# Sheet1.net
KiCad netlist of a schematic drawn in Altium Designer
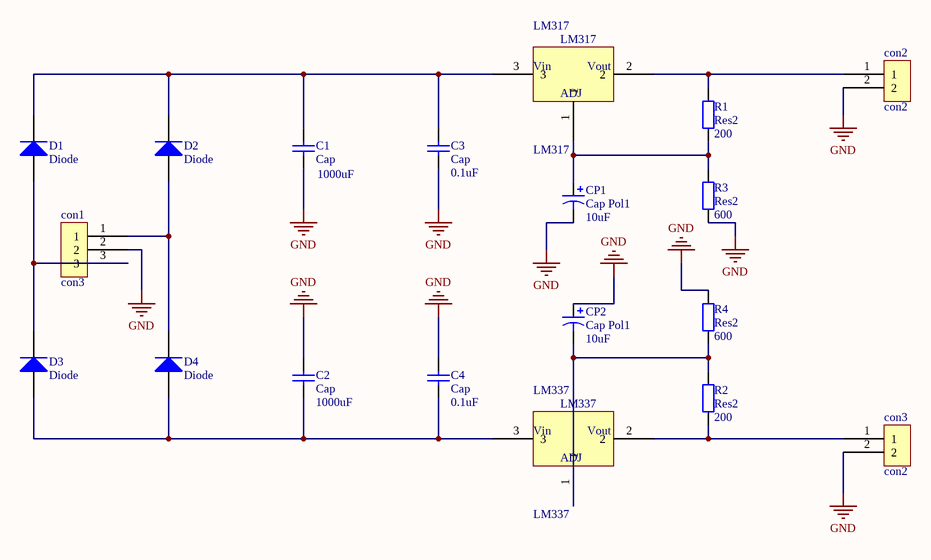
[diagram p0: Sheet1.SchDoc]

(export (version "E")
  (design (tool "Eeschema 10.0.6"))
  (components
    (comp (ref "C1")
      (value "Cap")
      (footprint "RAD-0.3")
      (description "Capacitor")
      (fields (field (name "ALTIUM_VALUE") "1000uF") (field (name "PUBLISHER") "Altium Limited"))
      (libsource (lib "Miscellaneous Devices") (part "Cap"))
    )
    (comp (ref "C2")
      (value "Cap")
      (footprint "RAD-0.3")
      (description "Capacitor")
      (fields (field (name "ALTIUM_VALUE") "1000uF") (field (name "PUBLISHER") "Altium Limited"))
      (libsource (lib "Miscellaneous Devices") (part "Cap"))
    )
    (comp (ref "C3")
      (value "Cap")
      (footprint "RAD-0.3")
      (description "Capacitor")
      (fields (field (name "ALTIUM_VALUE") "0.1uF") (field (name "PUBLISHER") "Altium Limited"))
      (libsource (lib "Miscellaneous Devices") (part "Cap"))
    )
    (comp (ref "C4")
      (value "Cap")
      (footprint "RAD-0.3")
      (description "Capacitor")
      (fields (field (name "ALTIUM_VALUE") "0.1uF") (field (name "PUBLISHER") "Altium Limited"))
      (libsource (lib "Miscellaneous Devices") (part "Cap"))
    )
    (comp (ref "con1") (value "con3") (footprint "con3") (libsource (lib "con3") (part "con3")))
    (comp (ref "con2") (value "con2") (footprint "con2") (libsource (lib "con2") (part "con2")))
    (comp (ref "con3") (value "con2") (footprint "con2") (libsource (lib "con2") (part "con2")))
    (comp (ref "CP1")
      (value "Cap Pol1")
      (footprint "RB7.6-15")
      (description "Polarized Capacitor (Radial)")
      (fields (field (name "ALTIUM_VALUE") "10uF") (field (name "PUBLISHER") "Altium Limited"))
      (libsource (lib "Miscellaneous Devices") (part "Cap Pol1"))
    )
    (comp (ref "CP2")
      (value "Cap Pol1")
      (footprint "RB7.6-15")
      (description "Polarized Capacitor (Radial)")
      (fields (field (name "ALTIUM_VALUE") "10uF") (field (name "PUBLISHER") "Altium Limited"))
      (libsource (lib "Miscellaneous Devices") (part "Cap Pol1"))
    )
    (comp (ref "D1")
      (value "Diode")
      (footprint "DIODE-0.4")
      (description "Default Diode")
      (fields (field (name "PUBLISHER") "Altium Limited"))
      (libsource (lib "Miscellaneous Devices") (part "Diode"))
    )
    (comp (ref "D2")
      (value "Diode")
      (footprint "DIODE-0.4")
      (description "Default Diode")
      (fields (field (name "PUBLISHER") "Altium Limited"))
      (libsource (lib "Miscellaneous Devices") (part "Diode"))
    )
    (comp (ref "D3")
      (value "Diode")
      (footprint "DIODE-0.4")
      (description "Default Diode")
      (fields (field (name "PUBLISHER") "Altium Limited"))
      (libsource (lib "Miscellaneous Devices") (part "Diode"))
    )
    (comp (ref "D4")
      (value "Diode")
      (footprint "DIODE-0.4")
      (description "Default Diode")
      (fields (field (name "PUBLISHER") "Altium Limited"))
      (libsource (lib "Miscellaneous Devices") (part "Diode"))
    )
    (comp (ref "LM317") (value "LM317") (footprint "TO-220-AB") (libsource (lib "LM317") (part "LM317")))
    (comp (ref "LM337") (value "LM337") (footprint "TO-220-AB") (libsource (lib "LM337") (part "LM337")))
    (comp (ref "R1")
      (value "Res2")
      (footprint "AXIAL-0.4")
      (description "Resistor")
      (fields (field (name "ALTIUM_VALUE") "200") (field (name "PUBLISHER") "Altium Limited"))
      (libsource (lib "Miscellaneous Devices") (part "Res2"))
    )
    (comp (ref "R2")
      (value "Res2")
      (footprint "AXIAL-0.4")
      (description "Resistor")
      (fields (field (name "ALTIUM_VALUE") "200") (field (name "PUBLISHER") "Altium Limited"))
      (libsource (lib "Miscellaneous Devices") (part "Res2"))
    )
    (comp (ref "R3")
      (value "Res2")
      (footprint "AXIAL-0.4")
      (description "Resistor")
      (fields (field (name "ALTIUM_VALUE") "600") (field (name "PUBLISHER") "Altium Limited"))
      (libsource (lib "Miscellaneous Devices") (part "Res2"))
    )
    (comp (ref "R4")
      (value "Res2")
      (footprint "AXIAL-0.4")
      (description "Resistor")
      (fields (field (name "ALTIUM_VALUE") "600") (field (name "PUBLISHER") "Altium Limited"))
      (libsource (lib "Miscellaneous Devices") (part "Res2"))
    )
  )
  (nets
    (net (code "1") (name "GND") (class "Default")
      (node (ref "C1") (pin "1") (pinfunction "1_1") (pintype "passive"))
      (node (ref "C2") (pin "2") (pinfunction "2_2") (pintype "passive"))
      (node (ref "C3") (pin "1") (pinfunction "1_1") (pintype "passive"))
      (node (ref "C4") (pin "2") (pinfunction "2_2") (pintype "passive"))
      (node (ref "CP1") (pin "2") (pinfunction "2_2") (pintype "passive"))
      (node (ref "CP2") (pin "1") (pinfunction "1_1") (pintype "passive"))
      (node (ref "R3") (pin "1") (pinfunction "1_1") (pintype "passive"))
      (node (ref "R4") (pin "2") (pinfunction "2_2") (pintype "passive"))
      (node (ref "con1") (pin "2") (pinfunction "2_2") (pintype "passive"))
      (node (ref "con2") (pin "2") (pinfunction "2_2") (pintype "passive"))
      (node (ref "con3") (pin "2") (pinfunction "2_2") (pintype "passive"))
    )
    (net (code "2") (name "Net-(CP1-Pad1)") (class "Default")
      (node (ref "CP1") (pin "1") (pinfunction "1_1") (pintype "passive"))
      (node (ref "LM317") (pin "1") (pinfunction "1_1") (pintype "passive"))
      (node (ref "R1") (pin "1") (pinfunction "1_1") (pintype "passive"))
      (node (ref "R3") (pin "2") (pinfunction "2_2") (pintype "passive"))
    )
    (net (code "3") (name "Net-(CP2-Pad2)") (class "Default")
      (node (ref "CP2") (pin "2") (pinfunction "2_2") (pintype "passive"))
      (node (ref "LM337") (pin "1") (pinfunction "1_1") (pintype "passive"))
      (node (ref "R2") (pin "2") (pinfunction "2_2") (pintype "passive"))
      (node (ref "R4") (pin "1") (pinfunction "1_1") (pintype "passive"))
    )
    (net (code "4") (name "Net-(D1-A)") (class "Default")
      (node (ref "D1") (pin "1") (pinfunction "A_1") (pintype "passive"))
      (node (ref "D3") (pin "2") (pinfunction "K_2") (pintype "passive"))
      (node (ref "con1") (pin "3") (pinfunction "3_3") (pintype "passive"))
    )
    (net (code "5") (name "Net-(D1-K)") (class "Default")
      (node (ref "C1") (pin "2") (pinfunction "2_2") (pintype "passive"))
      (node (ref "C3") (pin "2") (pinfunction "2_2") (pintype "passive"))
      (node (ref "D1") (pin "2") (pinfunction "K_2") (pintype "passive"))
      (node (ref "D2") (pin "2") (pinfunction "K_2") (pintype "passive"))
      (node (ref "LM317") (pin "3") (pinfunction "3_3") (pintype "passive"))
    )
    (net (code "6") (name "Net-(D2-A)") (class "Default")
      (node (ref "D2") (pin "1") (pinfunction "A_1") (pintype "passive"))
      (node (ref "D4") (pin "2") (pinfunction "K_2") (pintype "passive"))
      (node (ref "con1") (pin "1") (pinfunction "1_1") (pintype "passive"))
    )
    (net (code "7") (name "Net-(D3-A)") (class "Default")
      (node (ref "C2") (pin "1") (pinfunction "1_1") (pintype "passive"))
      (node (ref "C4") (pin "1") (pinfunction "1_1") (pintype "passive"))
      (node (ref "D3") (pin "1") (pinfunction "A_1") (pintype "passive"))
      (node (ref "D4") (pin "1") (pinfunction "A_1") (pintype "passive"))
      (node (ref "LM337") (pin "3") (pinfunction "3_3") (pintype "passive"))
    )
    (net (code "8") (name "Net-(LM317-Pad2)") (class "Default")
      (node (ref "LM317") (pin "2") (pinfunction "2_2") (pintype "passive"))
      (node (ref "R1") (pin "2") (pinfunction "2_2") (pintype "passive"))
      (node (ref "con2") (pin "1") (pinfunction "1_1") (pintype "passive"))
    )
    (net (code "9") (name "Net-(LM337-Pad2)") (class "Default")
      (node (ref "LM337") (pin "2") (pinfunction "2_2") (pintype "passive"))
      (node (ref "R2") (pin "1") (pinfunction "1_1") (pintype "passive"))
      (node (ref "con3") (pin "1") (pinfunction "1_1") (pintype "passive"))
    )
  )
)
